# Placa_Opto.net
KiCad netlist of a schematic drawn in EAGLE
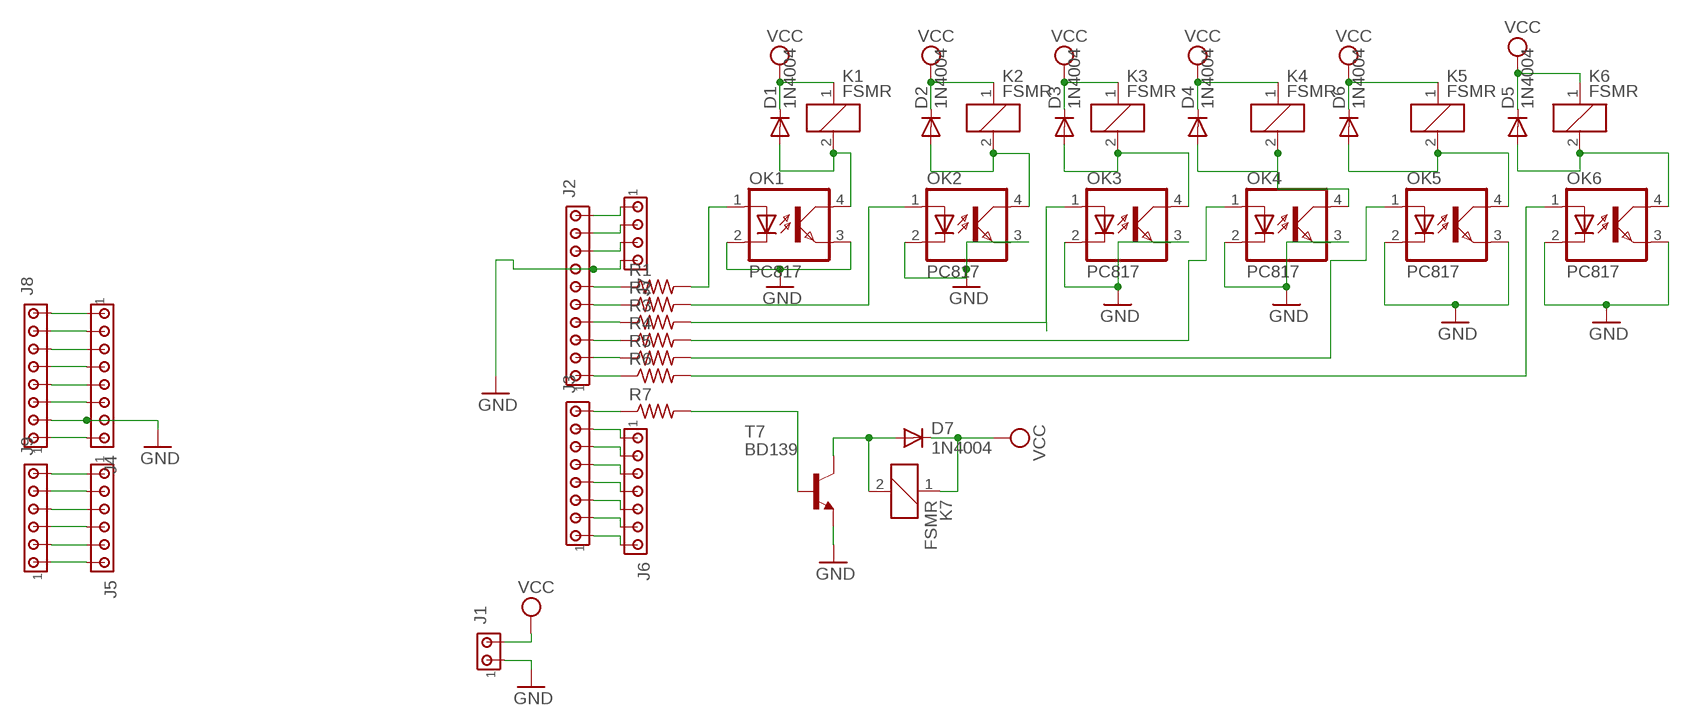
[diagram p0: schematic, sheet 1]

(export (version "E")
  (design (tool "Eeschema 10.0.6"))
  (components
    (comp (ref "D1")
      (value "1N4004")
      (footprint "eagle-import:DO41-10")
      (libsource (lib "eagle-import") (part "1N4004"))
    )
    (comp (ref "D2")
      (value "1N4004")
      (footprint "eagle-import:DO41-10")
      (libsource (lib "eagle-import") (part "1N4004"))
    )
    (comp (ref "D3")
      (value "1N4004")
      (footprint "eagle-import:DO41-10")
      (libsource (lib "eagle-import") (part "1N4004"))
    )
    (comp (ref "D4")
      (value "1N4004")
      (footprint "eagle-import:DO41-10")
      (libsource (lib "eagle-import") (part "1N4004"))
    )
    (comp (ref "D5")
      (value "1N4004")
      (footprint "eagle-import:DO41-10")
      (libsource (lib "eagle-import") (part "1N4004"))
    )
    (comp (ref "D6")
      (value "1N4004")
      (footprint "eagle-import:DO41-10")
      (libsource (lib "eagle-import") (part "1N4004"))
    )
    (comp (ref "D7")
      (value "1N4004")
      (footprint "eagle-import:DO41-10")
      (libsource (lib "eagle-import") (part "1N4004"))
    )
    (comp (ref "J1")
      (value "MTA02-156")
      (footprint "eagle-import:1X2MTA")
      (libsource (lib "eagle-import") (part "MTA02-156"))
    )
    (comp (ref "J2")
      (value "MTA10-100")
      (footprint "eagle-import:10X10MTA")
      (libsource (lib "eagle-import") (part "MTA10-100"))
    )
    (comp (ref "J3")
      (value "MTA08-100")
      (footprint "eagle-import:10X08MTA")
      (libsource (lib "eagle-import") (part "MTA08-100"))
    )
    (comp (ref "J4")
      (value "MTA08-100")
      (footprint "eagle-import:10X08MTA")
      (libsource (lib "eagle-import") (part "MTA08-100"))
    )
    (comp (ref "J5")
      (value "MTA06-100")
      (footprint "eagle-import:10X06MTA")
      (libsource (lib "eagle-import") (part "MTA06-100"))
    )
    (comp (ref "J6")
      (value "MTA07-100")
      (footprint "eagle-import:10X07MTA")
      (libsource (lib "eagle-import") (part "MTA07-100"))
    )
    (comp (ref "J7")
      (value "MTA04-100")
      (footprint "eagle-import:10X04MTA")
      (libsource (lib "eagle-import") (part "MTA04-100"))
    )
    (comp (ref "J8")
      (value "MTA08-100")
      (footprint "eagle-import:10X08MTA")
      (libsource (lib "eagle-import") (part "MTA08-100"))
    )
    (comp (ref "J9")
      (value "MTA06-100")
      (footprint "eagle-import:10X06MTA")
      (libsource (lib "eagle-import") (part "MTA06-100"))
    )
    (comp (ref "K1")
      (value "FSMR")
      (footprint "eagle-import:FSMR")
      (libsource (lib "eagle-import") (part "FSMR"))
    )
    (comp (ref "K2")
      (value "FSMR")
      (footprint "eagle-import:FSMR")
      (libsource (lib "eagle-import") (part "FSMR"))
    )
    (comp (ref "K3")
      (value "FSMR")
      (footprint "eagle-import:FSMR")
      (libsource (lib "eagle-import") (part "FSMR"))
    )
    (comp (ref "K4")
      (value "FSMR")
      (footprint "eagle-import:FSMR")
      (libsource (lib "eagle-import") (part "FSMR"))
    )
    (comp (ref "K5")
      (value "FSMR")
      (footprint "eagle-import:FSMR")
      (libsource (lib "eagle-import") (part "FSMR"))
    )
    (comp (ref "K6")
      (value "FSMR")
      (footprint "eagle-import:FSMR")
      (libsource (lib "eagle-import") (part "FSMR"))
    )
    (comp (ref "K7")
      (value "FSMR")
      (footprint "eagle-import:FSMR")
      (libsource (lib "eagle-import") (part "FSMR"))
    )
    (comp (ref "OK1")
      (value "PC817")
      (footprint "eagle-import:DIL04")
      (fields (field (name "MPN") "PC817X4J000F"))
      (libsource (lib "eagle-import") (part "PC817"))
    )
    (comp (ref "OK2")
      (value "PC817")
      (footprint "eagle-import:DIL04")
      (fields (field (name "MPN") "PC817X4J000F"))
      (libsource (lib "eagle-import") (part "PC817"))
    )
    (comp (ref "OK3")
      (value "PC817")
      (footprint "eagle-import:DIL04")
      (fields (field (name "MPN") "PC817X4J000F"))
      (libsource (lib "eagle-import") (part "PC817"))
    )
    (comp (ref "OK4")
      (value "PC817")
      (footprint "eagle-import:DIL04")
      (fields (field (name "MPN") "PC817X4J000F"))
      (libsource (lib "eagle-import") (part "PC817"))
    )
    (comp (ref "OK5")
      (value "PC817")
      (footprint "eagle-import:DIL04")
      (fields (field (name "MPN") "PC817X4J000F"))
      (libsource (lib "eagle-import") (part "PC817"))
    )
    (comp (ref "OK6")
      (value "PC817")
      (footprint "eagle-import:DIL04")
      (fields (field (name "MPN") "PC817X4J000F"))
      (libsource (lib "eagle-import") (part "PC817"))
    )
    (comp (ref "R1")
      (value "R-US_0207/10")
      (footprint "eagle-import:0207_10")
      (libsource (lib "eagle-import") (part "R-US_0207/10"))
    )
    (comp (ref "R2")
      (value "R-US_0207/10")
      (footprint "eagle-import:0207_10")
      (libsource (lib "eagle-import") (part "R-US_0207/10"))
    )
    (comp (ref "R3")
      (value "R-US_0207/10")
      (footprint "eagle-import:0207_10")
      (libsource (lib "eagle-import") (part "R-US_0207/10"))
    )
    (comp (ref "R4")
      (value "R-US_0207/10")
      (footprint "eagle-import:0207_10")
      (libsource (lib "eagle-import") (part "R-US_0207/10"))
    )
    (comp (ref "R5")
      (value "R-US_0207/10")
      (footprint "eagle-import:0207_10")
      (libsource (lib "eagle-import") (part "R-US_0207/10"))
    )
    (comp (ref "R6")
      (value "R-US_0207/10")
      (footprint "eagle-import:0207_10")
      (libsource (lib "eagle-import") (part "R-US_0207/10"))
    )
    (comp (ref "R7")
      (value "R-US_0207/10")
      (footprint "eagle-import:0207_10")
      (libsource (lib "eagle-import") (part "R-US_0207/10"))
    )
    (comp (ref "T7")
      (value "BD139")
      (footprint "eagle-import:TO126")
      (libsource (lib "eagle-import") (part "BD139"))
    )
  )
  (nets
    (net (code "1") (name "GND") (class "Default")
      (node (ref "J1") (pin "1") (pinfunction "1_1") (pintype "passive"))
      (node (ref "J2") (pin "7") (pinfunction "7_7") (pintype "passive"))
      (node (ref "J4") (pin "7") (pinfunction "7_7") (pintype "passive"))
      (node (ref "J7") (pin "4") (pinfunction "4_4") (pintype "passive"))
      (node (ref "J8") (pin "2") (pinfunction "2_2") (pintype "passive"))
      (node (ref "OK1") (pin "2") (pinfunction "C_2") (pintype "passive"))
      (node (ref "OK1") (pin "3") (pinfunction "EMIT_3") (pintype "passive"))
      (node (ref "OK2") (pin "2") (pinfunction "C_2") (pintype "passive"))
      (node (ref "OK2") (pin "3") (pinfunction "EMIT_3") (pintype "passive"))
      (node (ref "OK3") (pin "2") (pinfunction "C_2") (pintype "passive"))
      (node (ref "OK3") (pin "3") (pinfunction "EMIT_3") (pintype "passive"))
      (node (ref "OK4") (pin "2") (pinfunction "C_2") (pintype "passive"))
      (node (ref "OK4") (pin "3") (pinfunction "EMIT_3") (pintype "passive"))
      (node (ref "OK5") (pin "2") (pinfunction "C_2") (pintype "passive"))
      (node (ref "OK5") (pin "3") (pinfunction "EMIT_3") (pintype "passive"))
      (node (ref "OK6") (pin "2") (pinfunction "C_2") (pintype "passive"))
      (node (ref "OK6") (pin "3") (pinfunction "EMIT_3") (pintype "passive"))
      (node (ref "T7") (pin "1") (pinfunction "E_1") (pintype "passive"))
    )
    (net (code "2") (name "Net-(J2-Pad1)") (class "Default")
      (node (ref "J2") (pin "1") (pinfunction "1_1") (pintype "passive"))
      (node (ref "R6") (pin "1") (pinfunction "1_1") (pintype "passive"))
    )
    (net (code "3") (name "Net-(J2-Pad2)") (class "Default")
      (node (ref "J2") (pin "2") (pinfunction "2_2") (pintype "passive"))
      (node (ref "R5") (pin "1") (pinfunction "1_1") (pintype "passive"))
    )
    (net (code "4") (name "Net-(J2-Pad3)") (class "Default")
      (node (ref "J2") (pin "3") (pinfunction "3_3") (pintype "passive"))
      (node (ref "R4") (pin "1") (pinfunction "1_1") (pintype "passive"))
    )
    (net (code "5") (name "Net-(J2-Pad4)") (class "Default")
      (node (ref "J2") (pin "4") (pinfunction "4_4") (pintype "passive"))
      (node (ref "R3") (pin "1") (pinfunction "1_1") (pintype "passive"))
    )
    (net (code "6") (name "Net-(J2-Pad5)") (class "Default")
      (node (ref "J2") (pin "5") (pinfunction "5_5") (pintype "passive"))
      (node (ref "R2") (pin "1") (pinfunction "1_1") (pintype "passive"))
    )
    (net (code "7") (name "Net-(J2-Pad6)") (class "Default")
      (node (ref "J2") (pin "6") (pinfunction "6_6") (pintype "passive"))
      (node (ref "R1") (pin "1") (pinfunction "1_1") (pintype "passive"))
    )
    (net (code "8") (name "Net-(J2-Pad8)") (class "Default")
      (node (ref "J2") (pin "8") (pinfunction "8_8") (pintype "passive"))
      (node (ref "J7") (pin "3") (pinfunction "3_3") (pintype "passive"))
    )
    (net (code "9") (name "Net-(J2-Pad9)") (class "Default")
      (node (ref "J2") (pin "9") (pinfunction "9_9") (pintype "passive"))
      (node (ref "J7") (pin "2") (pinfunction "2_2") (pintype "passive"))
    )
    (net (code "10") (name "Net-(J2-Pad10)") (class "Default")
      (node (ref "J2") (pin "10") (pinfunction "10_10") (pintype "passive"))
      (node (ref "J7") (pin "1") (pinfunction "1_1") (pintype "passive"))
    )
    (net (code "11") (name "Net-(J3-Pad1)") (class "Default")
      (node (ref "J3") (pin "1") (pinfunction "1_1") (pintype "passive"))
      (node (ref "J6") (pin "7") (pinfunction "7_7") (pintype "passive"))
    )
    (net (code "12") (name "Net-(J3-Pad2)") (class "Default")
      (node (ref "J3") (pin "2") (pinfunction "2_2") (pintype "passive"))
      (node (ref "J6") (pin "6") (pinfunction "6_6") (pintype "passive"))
    )
    (net (code "13") (name "Net-(J3-Pad3)") (class "Default")
      (node (ref "J3") (pin "3") (pinfunction "3_3") (pintype "passive"))
      (node (ref "J6") (pin "5") (pinfunction "5_5") (pintype "passive"))
    )
    (net (code "14") (name "Net-(J3-Pad4)") (class "Default")
      (node (ref "J3") (pin "4") (pinfunction "4_4") (pintype "passive"))
      (node (ref "J6") (pin "4") (pinfunction "4_4") (pintype "passive"))
    )
    (net (code "15") (name "Net-(J3-Pad5)") (class "Default")
      (node (ref "J3") (pin "5") (pinfunction "5_5") (pintype "passive"))
      (node (ref "J6") (pin "3") (pinfunction "3_3") (pintype "passive"))
    )
    (net (code "16") (name "Net-(J3-Pad6)") (class "Default")
      (node (ref "J3") (pin "6") (pinfunction "6_6") (pintype "passive"))
      (node (ref "J6") (pin "2") (pinfunction "2_2") (pintype "passive"))
    )
    (net (code "17") (name "Net-(J3-Pad7)") (class "Default")
      (node (ref "J3") (pin "7") (pinfunction "7_7") (pintype "passive"))
      (node (ref "J6") (pin "1") (pinfunction "1_1") (pintype "passive"))
    )
    (net (code "18") (name "Net-(J3-Pad8)") (class "Default")
      (node (ref "J3") (pin "8") (pinfunction "8_8") (pintype "passive"))
      (node (ref "R7") (pin "1") (pinfunction "1_1") (pintype "passive"))
    )
    (net (code "19") (name "Net-(J4-Pad1)") (class "Default")
      (node (ref "J4") (pin "1") (pinfunction "1_1") (pintype "passive"))
      (node (ref "J8") (pin "8") (pinfunction "8_8") (pintype "passive"))
    )
    (net (code "20") (name "Net-(J4-Pad2)") (class "Default")
      (node (ref "J4") (pin "2") (pinfunction "2_2") (pintype "passive"))
      (node (ref "J8") (pin "7") (pinfunction "7_7") (pintype "passive"))
    )
    (net (code "21") (name "Net-(J4-Pad3)") (class "Default")
      (node (ref "J4") (pin "3") (pinfunction "3_3") (pintype "passive"))
      (node (ref "J8") (pin "6") (pinfunction "6_6") (pintype "passive"))
    )
    (net (code "22") (name "Net-(J4-Pad4)") (class "Default")
      (node (ref "J4") (pin "4") (pinfunction "4_4") (pintype "passive"))
      (node (ref "J8") (pin "5") (pinfunction "5_5") (pintype "passive"))
    )
    (net (code "23") (name "Net-(J4-Pad5)") (class "Default")
      (node (ref "J4") (pin "5") (pinfunction "5_5") (pintype "passive"))
      (node (ref "J8") (pin "4") (pinfunction "4_4") (pintype "passive"))
    )
    (net (code "24") (name "Net-(J4-Pad6)") (class "Default")
      (node (ref "J4") (pin "6") (pinfunction "6_6") (pintype "passive"))
      (node (ref "J8") (pin "3") (pinfunction "3_3") (pintype "passive"))
    )
    (net (code "25") (name "Net-(J4-Pad8)") (class "Default")
      (node (ref "J4") (pin "8") (pinfunction "8_8") (pintype "passive"))
      (node (ref "J8") (pin "1") (pinfunction "1_1") (pintype "passive"))
    )
    (net (code "26") (name "Net-(J5-Pad1)") (class "Default")
      (node (ref "J5") (pin "1") (pinfunction "1_1") (pintype "passive"))
      (node (ref "J9") (pin "6") (pinfunction "6_6") (pintype "passive"))
    )
    (net (code "27") (name "Net-(J5-Pad2)") (class "Default")
      (node (ref "J5") (pin "2") (pinfunction "2_2") (pintype "passive"))
      (node (ref "J9") (pin "5") (pinfunction "5_5") (pintype "passive"))
    )
    (net (code "28") (name "Net-(J5-Pad3)") (class "Default")
      (node (ref "J5") (pin "3") (pinfunction "3_3") (pintype "passive"))
      (node (ref "J9") (pin "4") (pinfunction "4_4") (pintype "passive"))
    )
    (net (code "29") (name "Net-(J5-Pad4)") (class "Default")
      (node (ref "J5") (pin "4") (pinfunction "4_4") (pintype "passive"))
      (node (ref "J9") (pin "3") (pinfunction "3_3") (pintype "passive"))
    )
    (net (code "30") (name "Net-(J5-Pad5)") (class "Default")
      (node (ref "J5") (pin "5") (pinfunction "5_5") (pintype "passive"))
      (node (ref "J9") (pin "2") (pinfunction "2_2") (pintype "passive"))
    )
    (net (code "31") (name "Net-(J5-Pad6)") (class "Default")
      (node (ref "J5") (pin "6") (pinfunction "6_6") (pintype "passive"))
      (node (ref "J9") (pin "1") (pinfunction "1_1") (pintype "passive"))
    )
    (net (code "32") (name "Net-(OK1-A)") (class "Default")
      (node (ref "OK1") (pin "1") (pinfunction "A_1") (pintype "passive"))
      (node (ref "R1") (pin "2") (pinfunction "2_2") (pintype "passive"))
    )
    (net (code "33") (name "Net-(OK1-COL)") (class "Default")
      (node (ref "D1") (pin "A") (pinfunction "A_A") (pintype "passive"))
      (node (ref "K1") (pin "2") (pinfunction "2_2") (pintype "passive"))
      (node (ref "OK1") (pin "4") (pinfunction "COL_4") (pintype "passive"))
    )
    (net (code "34") (name "Net-(OK2-A)") (class "Default")
      (node (ref "OK2") (pin "1") (pinfunction "A_1") (pintype "passive"))
      (node (ref "R2") (pin "2") (pinfunction "2_2") (pintype "passive"))
    )
    (net (code "35") (name "Net-(OK2-COL)") (class "Default")
      (node (ref "D2") (pin "A") (pinfunction "A_A") (pintype "passive"))
      (node (ref "K2") (pin "2") (pinfunction "2_2") (pintype "passive"))
      (node (ref "OK2") (pin "4") (pinfunction "COL_4") (pintype "passive"))
    )
    (net (code "36") (name "Net-(OK3-A)") (class "Default")
      (node (ref "OK3") (pin "1") (pinfunction "A_1") (pintype "passive"))
      (node (ref "R3") (pin "2") (pinfunction "2_2") (pintype "passive"))
    )
    (net (code "37") (name "Net-(OK3-COL)") (class "Default")
      (node (ref "D3") (pin "A") (pinfunction "A_A") (pintype "passive"))
      (node (ref "K3") (pin "2") (pinfunction "2_2") (pintype "passive"))
      (node (ref "OK3") (pin "4") (pinfunction "COL_4") (pintype "passive"))
    )
    (net (code "38") (name "Net-(OK4-A)") (class "Default")
      (node (ref "OK4") (pin "1") (pinfunction "A_1") (pintype "passive"))
      (node (ref "R4") (pin "2") (pinfunction "2_2") (pintype "passive"))
    )
    (net (code "39") (name "Net-(OK4-COL)") (class "Default")
      (node (ref "D4") (pin "A") (pinfunction "A_A") (pintype "passive"))
      (node (ref "K4") (pin "2") (pinfunction "2_2") (pintype "passive"))
      (node (ref "OK4") (pin "4") (pinfunction "COL_4") (pintype "passive"))
    )
    (net (code "40") (name "Net-(OK5-A)") (class "Default")
      (node (ref "OK5") (pin "1") (pinfunction "A_1") (pintype "passive"))
      (node (ref "R5") (pin "2") (pinfunction "2_2") (pintype "passive"))
    )
    (net (code "41") (name "Net-(OK5-COL)") (class "Default")
      (node (ref "D6") (pin "A") (pinfunction "A_A") (pintype "passive"))
      (node (ref "K5") (pin "2") (pinfunction "2_2") (pintype "passive"))
      (node (ref "OK5") (pin "4") (pinfunction "COL_4") (pintype "passive"))
    )
    (net (code "42") (name "Net-(OK6-A)") (class "Default")
      (node (ref "OK6") (pin "1") (pinfunction "A_1") (pintype "passive"))
      (node (ref "R6") (pin "2") (pinfunction "2_2") (pintype "passive"))
    )
    (net (code "43") (name "Net-(OK6-COL)") (class "Default")
      (node (ref "D5") (pin "A") (pinfunction "A_A") (pintype "passive"))
      (node (ref "K6") (pin "2") (pinfunction "2_2") (pintype "passive"))
      (node (ref "OK6") (pin "4") (pinfunction "COL_4") (pintype "passive"))
    )
    (net (code "44") (name "Net-(T7-B)") (class "Default")
      (node (ref "R7") (pin "2") (pinfunction "2_2") (pintype "passive"))
      (node (ref "T7") (pin "3") (pinfunction "B_3") (pintype "passive"))
    )
    (net (code "45") (name "Net-(T7-C)") (class "Default")
      (node (ref "D7") (pin "A") (pinfunction "A_A") (pintype "passive"))
      (node (ref "K7") (pin "2") (pinfunction "2_2") (pintype "passive"))
      (node (ref "T7") (pin "2") (pinfunction "C_2") (pintype "passive"))
    )
    (net (code "46") (name "VCC") (class "Default")
      (node (ref "D1") (pin "C") (pinfunction "C_C") (pintype "passive"))
      (node (ref "D2") (pin "C") (pinfunction "C_C") (pintype "passive"))
      (node (ref "D3") (pin "C") (pinfunction "C_C") (pintype "passive"))
      (node (ref "D4") (pin "C") (pinfunction "C_C") (pintype "passive"))
      (node (ref "D5") (pin "C") (pinfunction "C_C") (pintype "passive"))
      (node (ref "D6") (pin "C") (pinfunction "C_C") (pintype "passive"))
      (node (ref "D7") (pin "C") (pinfunction "C_C") (pintype "passive"))
      (node (ref "J1") (pin "2") (pinfunction "2_2") (pintype "passive"))
      (node (ref "K1") (pin "1") (pinfunction "1_1") (pintype "passive"))
      (node (ref "K2") (pin "1") (pinfunction "1_1") (pintype "passive"))
      (node (ref "K3") (pin "1") (pinfunction "1_1") (pintype "passive"))
      (node (ref "K4") (pin "1") (pinfunction "1_1") (pintype "passive"))
      (node (ref "K5") (pin "1") (pinfunction "1_1") (pintype "passive"))
      (node (ref "K6") (pin "1") (pinfunction "1_1") (pintype "passive"))
      (node (ref "K7") (pin "1") (pinfunction "1_1") (pintype "passive"))
    )
  )
)
